# STAC_Test_Board_v1_SwitchesButtons.net
KiCad netlist of a schematic drawn in Altium Designer
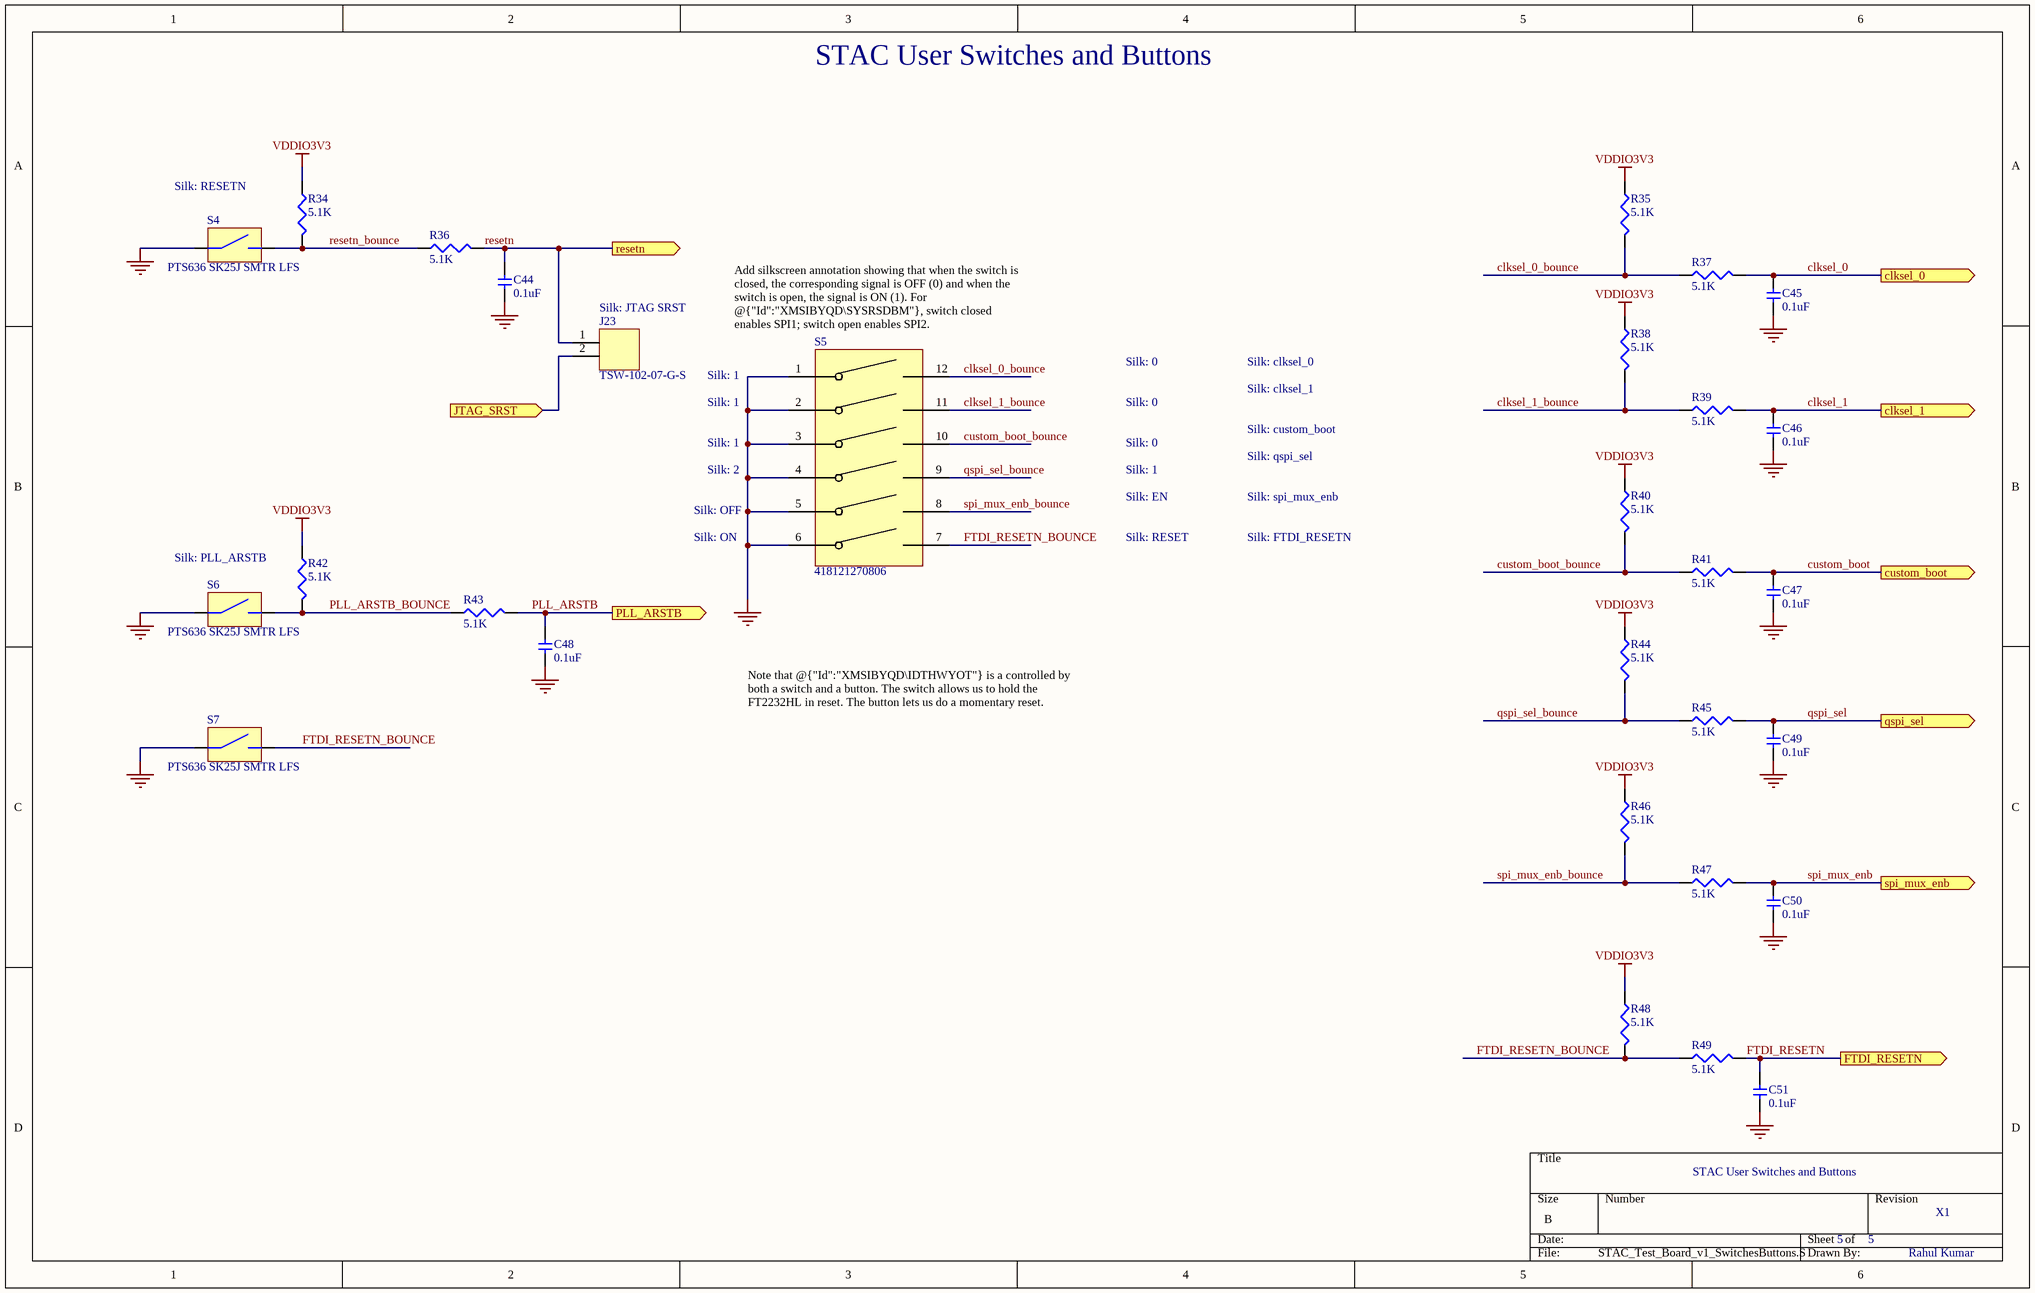
[diagram p0: STAC_Test_Board_v1_SwitchesButtons.SchDoc]

(export (version "E")
  (design (tool "Eeschema 10.0.6"))
  (components
    (comp (ref "C44")
      (value "0.1uF")
      (footprint "BWRC:0603")
      (description "Capacitor generic")
      (libsource (lib "BWRC") (part "DISCRETE_C"))
    )
    (comp (ref "C45")
      (value "0.1uF")
      (footprint "BWRC:0603")
      (description "Capacitor generic")
      (libsource (lib "BWRC") (part "DISCRETE_C"))
    )
    (comp (ref "C46")
      (value "0.1uF")
      (footprint "BWRC:0603")
      (description "Capacitor generic")
      (libsource (lib "BWRC") (part "DISCRETE_C"))
    )
    (comp (ref "C47")
      (value "0.1uF")
      (footprint "BWRC:0603")
      (description "Capacitor generic")
      (libsource (lib "BWRC") (part "DISCRETE_C"))
    )
    (comp (ref "C48")
      (value "0.1uF")
      (footprint "BWRC:0603")
      (description "Capacitor generic")
      (libsource (lib "BWRC") (part "DISCRETE_C"))
    )
    (comp (ref "C49")
      (value "0.1uF")
      (footprint "BWRC:0603")
      (description "Capacitor generic")
      (libsource (lib "BWRC") (part "DISCRETE_C"))
    )
    (comp (ref "C50")
      (value "0.1uF")
      (footprint "BWRC:0603")
      (description "Capacitor generic")
      (libsource (lib "BWRC") (part "DISCRETE_C"))
    )
    (comp (ref "C51")
      (value "0.1uF")
      (footprint "BWRC:0603")
      (description "Capacitor generic")
      (libsource (lib "BWRC") (part "DISCRETE_C"))
    )
    (comp (ref "J23")
      (value "TSW-102-07-G-S")
      (footprint "CON-002-100-200X100/1X2-POST")
      (description "Con 2 pins")
      (libsource (lib "BWRC") (part "CON_002pin_1x2"))
    )
    (comp (ref "R34")
      (value "5.1K")
      (footprint "BWRC:0603")
      (description "Resistor generic")
      (libsource (lib "BWRC") (part "DISCRETE_R"))
    )
    (comp (ref "R35")
      (value "5.1K")
      (footprint "BWRC:0603")
      (description "Resistor generic")
      (libsource (lib "BWRC") (part "DISCRETE_R"))
    )
    (comp (ref "R36")
      (value "5.1K")
      (footprint "BWRC:0603")
      (description "Resistor generic")
      (libsource (lib "BWRC") (part "DISCRETE_R"))
    )
    (comp (ref "R37")
      (value "5.1K")
      (footprint "BWRC:0603")
      (description "Resistor generic")
      (libsource (lib "BWRC") (part "DISCRETE_R"))
    )
    (comp (ref "R38")
      (value "5.1K")
      (footprint "BWRC:0603")
      (description "Resistor generic")
      (libsource (lib "BWRC") (part "DISCRETE_R"))
    )
    (comp (ref "R39")
      (value "5.1K")
      (footprint "BWRC:0603")
      (description "Resistor generic")
      (libsource (lib "BWRC") (part "DISCRETE_R"))
    )
    (comp (ref "R40")
      (value "5.1K")
      (footprint "BWRC:0603")
      (description "Resistor generic")
      (libsource (lib "BWRC") (part "DISCRETE_R"))
    )
    (comp (ref "R41")
      (value "5.1K")
      (footprint "BWRC:0603")
      (description "Resistor generic")
      (libsource (lib "BWRC") (part "DISCRETE_R"))
    )
    (comp (ref "R42")
      (value "5.1K")
      (footprint "BWRC:0603")
      (description "Resistor generic")
      (libsource (lib "BWRC") (part "DISCRETE_R"))
    )
    (comp (ref "R43")
      (value "5.1K")
      (footprint "BWRC:0603")
      (description "Resistor generic")
      (libsource (lib "BWRC") (part "DISCRETE_R"))
    )
    (comp (ref "R44")
      (value "5.1K")
      (footprint "BWRC:0603")
      (description "Resistor generic")
      (libsource (lib "BWRC") (part "DISCRETE_R"))
    )
    (comp (ref "R45")
      (value "5.1K")
      (footprint "BWRC:0603")
      (description "Resistor generic")
      (libsource (lib "BWRC") (part "DISCRETE_R"))
    )
    (comp (ref "R46")
      (value "5.1K")
      (footprint "BWRC:0603")
      (description "Resistor generic")
      (libsource (lib "BWRC") (part "DISCRETE_R"))
    )
    (comp (ref "R47")
      (value "5.1K")
      (footprint "BWRC:0603")
      (description "Resistor generic")
      (libsource (lib "BWRC") (part "DISCRETE_R"))
    )
    (comp (ref "R48")
      (value "5.1K")
      (footprint "BWRC:0603")
      (description "Resistor generic")
      (libsource (lib "BWRC") (part "DISCRETE_R"))
    )
    (comp (ref "R49")
      (value "5.1K")
      (footprint "BWRC:0603")
      (description "Resistor generic")
      (libsource (lib "BWRC") (part "DISCRETE_R"))
    )
    (comp (ref "S4")
      (value "PTS636 SK25J SMTR LFS")
      (footprint "SW-02-6.7X3.7")
      (description "Switch 2 pins")
      (libsource (lib "BWRC") (part "SWITCH_SPST_2pin"))
    )
    (comp (ref "S5")
      (value "418121270806")
      (footprint "GW-12-100-390")
      (description "SWITCH DIP SPST x6")
      (libsource (lib "BWRC") (part "SWITCH_SPST_x6"))
    )
    (comp (ref "S6")
      (value "PTS636 SK25J SMTR LFS")
      (footprint "SW-02-6.7X3.7")
      (description "Switch 2 pins")
      (libsource (lib "BWRC") (part "SWITCH_SPST_2pin"))
    )
    (comp (ref "S7")
      (value "PTS636 SK25J SMTR LFS")
      (footprint "SW-02-6.7X3.7")
      (description "Switch 2 pins")
      (libsource (lib "BWRC") (part "SWITCH_SPST_2pin"))
    )
  )
  (nets
    (net (code "1") (name "/FTDI_RESETN") (class "Default")
      (node (ref "C51") (pin "1") (pinfunction "1_1") (pintype "passive"))
      (node (ref "R49") (pin "2") (pinfunction "2_2") (pintype "passive"))
    )
    (net (code "2") (name "/FTDI_RESETN_BOUNCE") (class "Default")
      (node (ref "R48") (pin "2") (pinfunction "2_2") (pintype "passive"))
      (node (ref "R49") (pin "1") (pinfunction "1_1") (pintype "passive"))
      (node (ref "S5") (pin "7") (pintype "passive"))
      (node (ref "S7") (pin "1") (pinfunction "1_1") (pintype "passive"))
    )
    (net (code "3") (name "/JTAG_SRST") (class "Default")
      (node (ref "J23") (pin "2") (pinfunction "2_2") (pintype "passive"))
    )
    (net (code "4") (name "/PLL_ARSTB") (class "Default")
      (node (ref "C48") (pin "1") (pinfunction "1_1") (pintype "passive"))
      (node (ref "R43") (pin "2") (pinfunction "2_2") (pintype "passive"))
    )
    (net (code "5") (name "/PLL_ARSTB_BOUNCE") (class "Default")
      (node (ref "R42") (pin "2") (pinfunction "2_2") (pintype "passive"))
      (node (ref "R43") (pin "1") (pinfunction "1_1") (pintype "passive"))
      (node (ref "S6") (pin "1") (pinfunction "1_1") (pintype "passive"))
    )
    (net (code "6") (name "/clksel_0") (class "Default")
      (node (ref "C45") (pin "1") (pinfunction "1_1") (pintype "passive"))
      (node (ref "R37") (pin "2") (pinfunction "2_2") (pintype "passive"))
    )
    (net (code "7") (name "/clksel_0_bounce") (class "Default")
      (node (ref "R35") (pin "2") (pinfunction "2_2") (pintype "passive"))
      (node (ref "R37") (pin "1") (pinfunction "1_1") (pintype "passive"))
      (node (ref "S5") (pin "12") (pintype "passive"))
    )
    (net (code "8") (name "/clksel_1") (class "Default")
      (node (ref "C46") (pin "1") (pinfunction "1_1") (pintype "passive"))
      (node (ref "R39") (pin "2") (pinfunction "2_2") (pintype "passive"))
    )
    (net (code "9") (name "/clksel_1_bounce") (class "Default")
      (node (ref "R38") (pin "2") (pinfunction "2_2") (pintype "passive"))
      (node (ref "R39") (pin "1") (pinfunction "1_1") (pintype "passive"))
      (node (ref "S5") (pin "11") (pintype "passive"))
    )
    (net (code "10") (name "/custom_boot") (class "Default")
      (node (ref "C47") (pin "1") (pinfunction "1_1") (pintype "passive"))
      (node (ref "R41") (pin "2") (pinfunction "2_2") (pintype "passive"))
    )
    (net (code "11") (name "/custom_boot_bounce") (class "Default")
      (node (ref "R40") (pin "2") (pinfunction "2_2") (pintype "passive"))
      (node (ref "R41") (pin "1") (pinfunction "1_1") (pintype "passive"))
      (node (ref "S5") (pin "10") (pintype "passive"))
    )
    (net (code "12") (name "/qspi_sel") (class "Default")
      (node (ref "C49") (pin "1") (pinfunction "1_1") (pintype "passive"))
      (node (ref "R45") (pin "2") (pinfunction "2_2") (pintype "passive"))
    )
    (net (code "13") (name "/qspi_sel_bounce") (class "Default")
      (node (ref "R44") (pin "2") (pinfunction "2_2") (pintype "passive"))
      (node (ref "R45") (pin "1") (pinfunction "1_1") (pintype "passive"))
      (node (ref "S5") (pin "9") (pintype "passive"))
    )
    (net (code "14") (name "/resetn") (class "Default")
      (node (ref "C44") (pin "1") (pinfunction "1_1") (pintype "passive"))
      (node (ref "J23") (pin "1") (pinfunction "1_1") (pintype "passive"))
      (node (ref "R36") (pin "2") (pinfunction "2_2") (pintype "passive"))
    )
    (net (code "15") (name "/resetn_bounce") (class "Default")
      (node (ref "R34") (pin "2") (pinfunction "2_2") (pintype "passive"))
      (node (ref "R36") (pin "1") (pinfunction "1_1") (pintype "passive"))
      (node (ref "S4") (pin "1") (pinfunction "1_1") (pintype "passive"))
    )
    (net (code "16") (name "/spi_mux_enb") (class "Default")
      (node (ref "C50") (pin "1") (pinfunction "1_1") (pintype "passive"))
      (node (ref "R47") (pin "2") (pinfunction "2_2") (pintype "passive"))
    )
    (net (code "17") (name "/spi_mux_enb_bounce") (class "Default")
      (node (ref "R46") (pin "2") (pinfunction "2_2") (pintype "passive"))
      (node (ref "R47") (pin "1") (pinfunction "1_1") (pintype "passive"))
      (node (ref "S5") (pin "8") (pintype "passive"))
    )
    (net (code "18") (name "GND") (class "Default")
      (node (ref "C44") (pin "2") (pinfunction "2_2") (pintype "passive"))
      (node (ref "C45") (pin "2") (pinfunction "2_2") (pintype "passive"))
      (node (ref "C46") (pin "2") (pinfunction "2_2") (pintype "passive"))
      (node (ref "C47") (pin "2") (pinfunction "2_2") (pintype "passive"))
      (node (ref "C48") (pin "2") (pinfunction "2_2") (pintype "passive"))
      (node (ref "C49") (pin "2") (pinfunction "2_2") (pintype "passive"))
      (node (ref "C50") (pin "2") (pinfunction "2_2") (pintype "passive"))
      (node (ref "C51") (pin "2") (pinfunction "2_2") (pintype "passive"))
      (node (ref "S4") (pin "2") (pinfunction "2_2") (pintype "passive"))
      (node (ref "S5") (pin "1") (pintype "passive"))
      (node (ref "S5") (pin "2") (pintype "passive"))
      (node (ref "S5") (pin "3") (pintype "passive"))
      (node (ref "S5") (pin "4") (pintype "passive"))
      (node (ref "S5") (pin "5") (pintype "passive"))
      (node (ref "S5") (pin "6") (pintype "passive"))
      (node (ref "S6") (pin "2") (pinfunction "2_2") (pintype "passive"))
      (node (ref "S7") (pin "2") (pinfunction "2_2") (pintype "passive"))
    )
    (net (code "19") (name "VDDIO3V3") (class "Default")
      (node (ref "R34") (pin "1") (pinfunction "1_1") (pintype "passive"))
      (node (ref "R35") (pin "1") (pinfunction "1_1") (pintype "passive"))
      (node (ref "R38") (pin "1") (pinfunction "1_1") (pintype "passive"))
      (node (ref "R40") (pin "1") (pinfunction "1_1") (pintype "passive"))
      (node (ref "R42") (pin "1") (pinfunction "1_1") (pintype "passive"))
      (node (ref "R44") (pin "1") (pinfunction "1_1") (pintype "passive"))
      (node (ref "R46") (pin "1") (pinfunction "1_1") (pintype "passive"))
      (node (ref "R48") (pin "1") (pinfunction "1_1") (pintype "passive"))
    )
  )
)
